# ear-o_devboard.net
KiCad netlist of a schematic drawn in EAGLE
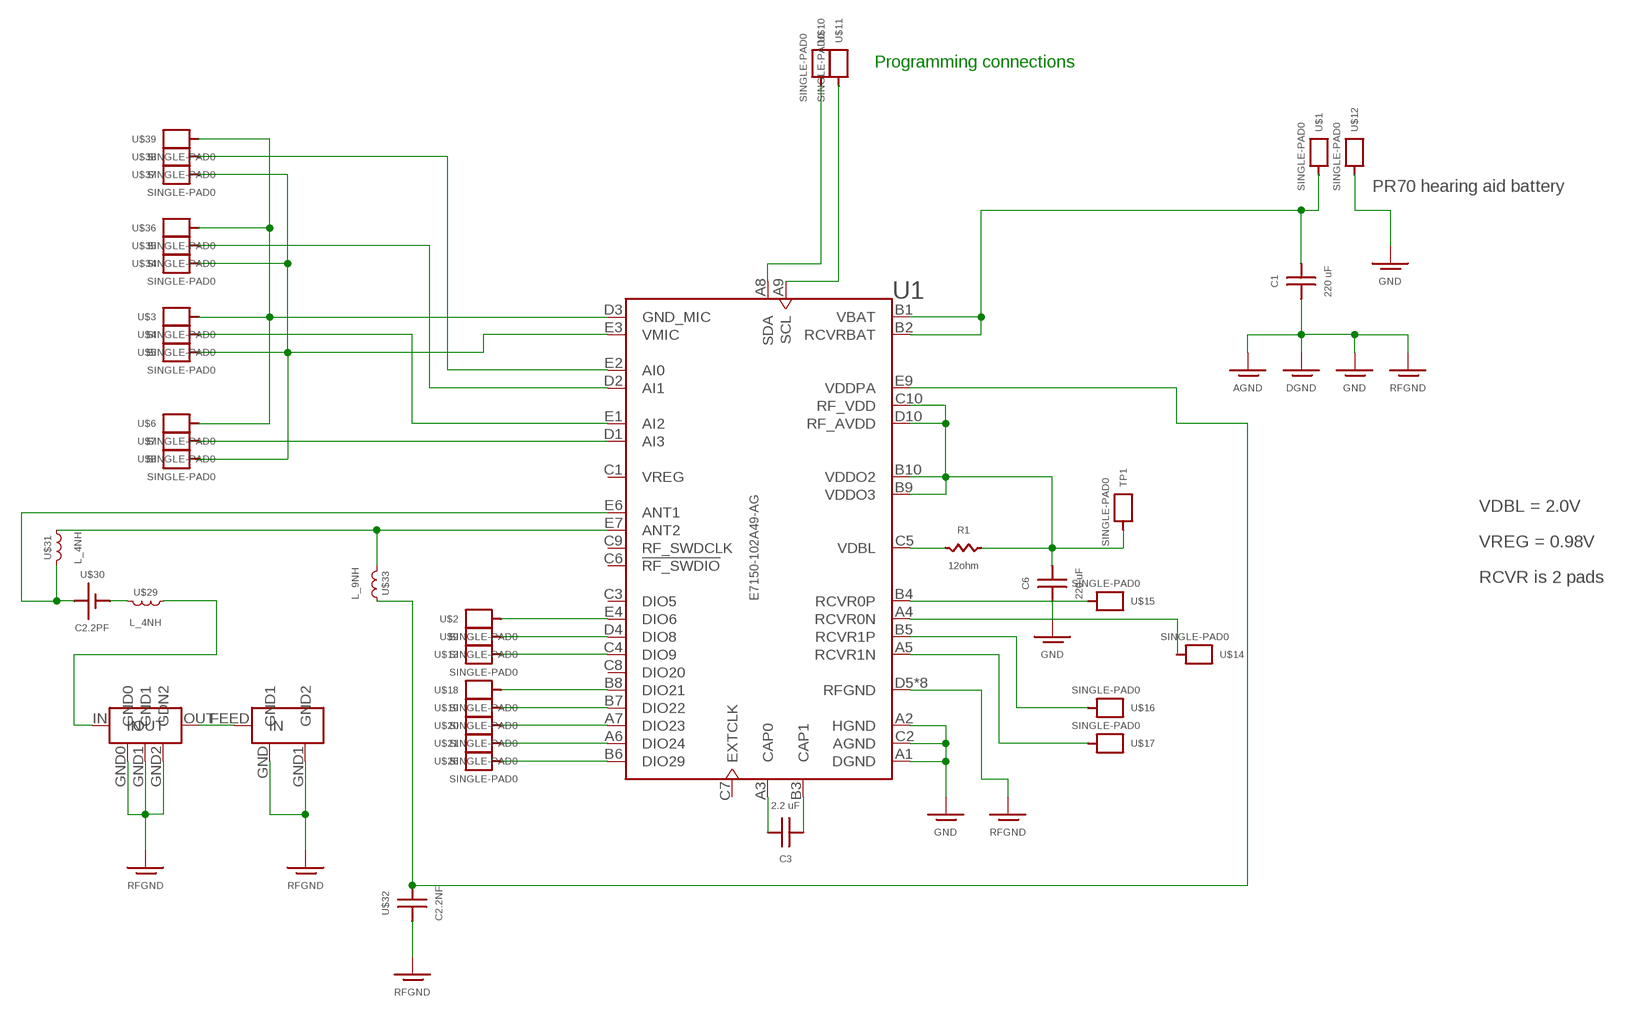
[diagram p0: schematic, sheet 1]

(export (version "E")
  (design (tool "Eeschema 10.0.6"))
  (components
    (comp (ref "C1")
      (value "220 uF")
      (footprint "eagle-import:1206")
      (libsource (lib "eagle-import") (part "C220UF"))
    )
    (comp (ref "C3")
      (value "2.2 uF")
      (footprint "eagle-import:0201")
      (libsource (lib "eagle-import") (part "C2.2UF"))
    )
    (comp (ref "C6")
      (value "220 uF")
      (footprint "eagle-import:1206")
      (libsource (lib "eagle-import") (part "C220UF"))
    )
    (comp (ref "R1")
      (value "12ohm")
      (footprint "eagle-import:0201")
      (libsource (lib "eagle-import") (part "R12OHM"))
    )
    (comp (ref "TP1")
      (value "SINGLE-PAD0")
      (footprint "eagle-import:TH")
      (libsource (lib "eagle-import") (part "SINGLE-PAD0"))
    )
    (comp (ref "U$1")
      (value "SINGLE-PAD0")
      (footprint "eagle-import:TH")
      (libsource (lib "eagle-import") (part "SINGLE-PAD0"))
    )
    (comp (ref "U$2")
      (value "SINGLE-PAD0")
      (footprint "eagle-import:TH")
      (libsource (lib "eagle-import") (part "SINGLE-PAD0"))
    )
    (comp (ref "U$3")
      (value "SINGLE-PAD0")
      (footprint "eagle-import:TH")
      (libsource (lib "eagle-import") (part "SINGLE-PAD0"))
    )
    (comp (ref "U$4")
      (value "SINGLE-PAD0")
      (footprint "eagle-import:TH")
      (libsource (lib "eagle-import") (part "SINGLE-PAD0"))
    )
    (comp (ref "U$5")
      (value "SINGLE-PAD0")
      (footprint "eagle-import:TH")
      (libsource (lib "eagle-import") (part "SINGLE-PAD0"))
    )
    (comp (ref "U$6")
      (value "SINGLE-PAD0")
      (footprint "eagle-import:TH")
      (libsource (lib "eagle-import") (part "SINGLE-PAD0"))
    )
    (comp (ref "U$7")
      (value "SINGLE-PAD0")
      (footprint "eagle-import:TH")
      (libsource (lib "eagle-import") (part "SINGLE-PAD0"))
    )
    (comp (ref "U$8")
      (value "SINGLE-PAD0")
      (footprint "eagle-import:TH")
      (libsource (lib "eagle-import") (part "SINGLE-PAD0"))
    )
    (comp (ref "U$9")
      (value "SINGLE-PAD0")
      (footprint "eagle-import:TH")
      (libsource (lib "eagle-import") (part "SINGLE-PAD0"))
    )
    (comp (ref "U$10")
      (value "SINGLE-PAD0")
      (footprint "eagle-import:TH")
      (libsource (lib "eagle-import") (part "SINGLE-PAD0"))
    )
    (comp (ref "U$11")
      (value "SINGLE-PAD0")
      (footprint "eagle-import:TH")
      (libsource (lib "eagle-import") (part "SINGLE-PAD0"))
    )
    (comp (ref "U$12")
      (value "SINGLE-PAD0")
      (footprint "eagle-import:TH")
      (libsource (lib "eagle-import") (part "SINGLE-PAD0"))
    )
    (comp (ref "U$13")
      (value "SINGLE-PAD0")
      (footprint "eagle-import:TH")
      (libsource (lib "eagle-import") (part "SINGLE-PAD0"))
    )
    (comp (ref "U$14")
      (value "SINGLE-PAD0")
      (footprint "eagle-import:TH")
      (libsource (lib "eagle-import") (part "SINGLE-PAD0"))
    )
    (comp (ref "U$15")
      (value "SINGLE-PAD0")
      (footprint "eagle-import:TH")
      (libsource (lib "eagle-import") (part "SINGLE-PAD0"))
    )
    (comp (ref "U$16")
      (value "SINGLE-PAD0")
      (footprint "eagle-import:TH")
      (libsource (lib "eagle-import") (part "SINGLE-PAD0"))
    )
    (comp (ref "U$17")
      (value "SINGLE-PAD0")
      (footprint "eagle-import:TH")
      (libsource (lib "eagle-import") (part "SINGLE-PAD0"))
    )
    (comp (ref "U$18")
      (value "SINGLE-PAD0")
      (footprint "eagle-import:TH")
      (libsource (lib "eagle-import") (part "SINGLE-PAD0"))
    )
    (comp (ref "U$19")
      (value "SINGLE-PAD0")
      (footprint "eagle-import:TH")
      (libsource (lib "eagle-import") (part "SINGLE-PAD0"))
    )
    (comp (ref "U$20")
      (value "SINGLE-PAD0")
      (footprint "eagle-import:TH")
      (libsource (lib "eagle-import") (part "SINGLE-PAD0"))
    )
    (comp (ref "U$21")
      (value "SINGLE-PAD0")
      (footprint "eagle-import:TH")
      (libsource (lib "eagle-import") (part "SINGLE-PAD0"))
    )
    (comp (ref "U$26")
      (value "SINGLE-PAD0")
      (footprint "eagle-import:TH")
      (libsource (lib "eagle-import") (part "SINGLE-PAD0"))
    )
    (comp (ref "U$27")
      (value "CHIP_ANT")
      (footprint "eagle-import:W3008")
      (libsource (lib "eagle-import") (part "CHIP_ANT"))
    )
    (comp (ref "U$28")
      (value "RF_FILT")
      (footprint "eagle-import:BPFILT")
      (libsource (lib "eagle-import") (part "RF_FILT"))
    )
    (comp (ref "U$29")
      (value "L_4NH")
      (footprint "eagle-import:0402")
      (libsource (lib "eagle-import") (part "L_4NH"))
    )
    (comp (ref "U$30")
      (value "C2.2PF")
      (footprint "eagle-import:0201")
      (libsource (lib "eagle-import") (part "C2.2PF"))
    )
    (comp (ref "U$31")
      (value "L_4NH")
      (footprint "eagle-import:0402")
      (libsource (lib "eagle-import") (part "L_4NH"))
    )
    (comp (ref "U$32")
      (value "C2.2NF")
      (footprint "eagle-import:0201")
      (libsource (lib "eagle-import") (part "C2.2NF"))
    )
    (comp (ref "U$33")
      (value "L_9NH")
      (footprint "eagle-import:0402")
      (libsource (lib "eagle-import") (part "L_9NH"))
    )
    (comp (ref "U$34")
      (value "SINGLE-PAD0")
      (footprint "eagle-import:TH")
      (libsource (lib "eagle-import") (part "SINGLE-PAD0"))
    )
    (comp (ref "U$35")
      (value "SINGLE-PAD0")
      (footprint "eagle-import:TH")
      (libsource (lib "eagle-import") (part "SINGLE-PAD0"))
    )
    (comp (ref "U$36")
      (value "SINGLE-PAD0")
      (footprint "eagle-import:TH")
      (libsource (lib "eagle-import") (part "SINGLE-PAD0"))
    )
    (comp (ref "U$37")
      (value "SINGLE-PAD0")
      (footprint "eagle-import:TH")
      (libsource (lib "eagle-import") (part "SINGLE-PAD0"))
    )
    (comp (ref "U$38")
      (value "SINGLE-PAD0")
      (footprint "eagle-import:TH")
      (libsource (lib "eagle-import") (part "SINGLE-PAD0"))
    )
    (comp (ref "U$39")
      (value "SINGLE-PAD0")
      (footprint "eagle-import:TH")
      (libsource (lib "eagle-import") (part "SINGLE-PAD0"))
    )
    (comp (ref "U1")
      (value "E7150-102A49-AG")
      (footprint "eagle-import:BGA49C69P10X5_739X394X178")
      (fields (field (name "MANUFACTURER") "ON Semiconductor"))
      (libsource (lib "eagle-import") (part "E7150-102A49-AG"))
    )
  )
  (nets
    (net (code "1") (name "/VREG") (class "Default")
      (node (ref "U1") (pin "C1") (pinfunction "VREG_C1") (pintype "power_in"))
    )
    (net (code "2") (name "AGND") (class "Default")
      (node (ref "C1") (pin "P$1") (pinfunction "1_P$1") (pintype "passive"))
      (node (ref "C6") (pin "P$1") (pinfunction "1_P$1") (pintype "passive"))
      (node (ref "U$12") (pin "P$1") (pinfunction "1_P$1") (pintype "bidirectional"))
      (node (ref "U$27") (pin "GND") (pinfunction "GND1_GND") (pintype "bidirectional"))
      (node (ref "U$27") (pin "GND1") (pinfunction "GND2_GND1") (pintype "bidirectional"))
      (node (ref "U$28") (pin "GND0") (pinfunction "GND0_GND0") (pintype "bidirectional"))
      (node (ref "U$28") (pin "GND1") (pinfunction "GND1_GND1") (pintype "bidirectional"))
      (node (ref "U$28") (pin "GND2") (pinfunction "GDN2_GND2") (pintype "bidirectional"))
      (node (ref "U$29") (pin "2") (pinfunction "2_2") (pintype "passive"))
      (node (ref "U$30") (pin "P$1") (pinfunction "GND_P$1") (pintype "power_in"))
      (node (ref "U$32") (pin "P$1") (pinfunction "1_P$1") (pintype "passive"))
      (node (ref "U1") (pin "A1") (pinfunction "DGND_A1") (pintype "power_in"))
      (node (ref "U1") (pin "A2") (pinfunction "HGND_A2") (pintype "power_in"))
      (node (ref "U1") (pin "C2") (pinfunction "AGND_C2") (pintype "power_in"))
      (node (ref "U1") (pin "D5") (pinfunction "RFGND_D5") (pintype "power_in"))
      (node (ref "U1") (pin "D6") (pinfunction "RFGND_D6") (pintype "power_in"))
      (node (ref "U1") (pin "D7") (pinfunction "RFGND_D7") (pintype "power_in"))
      (node (ref "U1") (pin "D8") (pinfunction "RFGND_D8") (pintype "power_in"))
      (node (ref "U1") (pin "D9") (pinfunction "RFGND_D9") (pintype "power_in"))
      (node (ref "U1") (pin "E10") (pinfunction "RFGND_E10") (pintype "power_in"))
      (node (ref "U1") (pin "E5") (pinfunction "RFGND_E5") (pintype "power_in"))
      (node (ref "U1") (pin "E8") (pinfunction "RFGND_E8") (pintype "power_in"))
    )
    (net (code "3") (name "Net-(C1-2)") (class "Default")
      (node (ref "C1") (pin "P$2") (pinfunction "2_P$2") (pintype "passive"))
      (node (ref "U$1") (pin "P$1") (pinfunction "1_P$1") (pintype "bidirectional"))
      (node (ref "U1") (pin "B1") (pinfunction "VBAT_B1") (pintype "power_in"))
      (node (ref "U1") (pin "B2") (pinfunction "RCVRBAT_B2") (pintype "power_in"))
    )
    (net (code "4") (name "Net-(C3-1)") (class "Default")
      (node (ref "C3") (pin "P$1") (pinfunction "1_P$1") (pintype "passive"))
      (node (ref "U1") (pin "B3") (pinfunction "CAP1_B3") (pintype "bidirectional"))
    )
    (net (code "5") (name "Net-(C3-2)") (class "Default")
      (node (ref "C3") (pin "P$2") (pinfunction "2_P$2") (pintype "passive"))
      (node (ref "U1") (pin "A3") (pinfunction "CAP0_A3") (pintype "bidirectional"))
    )
    (net (code "6") (name "Net-(C6-2)") (class "Default")
      (node (ref "C6") (pin "P$2") (pinfunction "2_P$2") (pintype "passive"))
      (node (ref "R1") (pin "P$2") (pinfunction "P$2_P$2") (pintype "bidirectional"))
      (node (ref "TP1") (pin "P$1") (pinfunction "1_P$1") (pintype "bidirectional"))
      (node (ref "U1") (pin "B10") (pinfunction "VDDO2_B10") (pintype "power_in"))
      (node (ref "U1") (pin "B9") (pinfunction "VDDO3_B9") (pintype "power_in"))
      (node (ref "U1") (pin "C10") (pinfunction "RF_VDD_C10") (pintype "power_in"))
      (node (ref "U1") (pin "D10") (pinfunction "RF_AVDD_D10") (pintype "power_in"))
    )
    (net (code "7") (name "Net-(U$2-1)") (class "Default")
      (node (ref "U$2") (pin "P$1") (pinfunction "1_P$1") (pintype "bidirectional"))
      (node (ref "U1") (pin "E4") (pinfunction "DIO6_E4") (pintype "bidirectional"))
    )
    (net (code "8") (name "Net-(U$3-1)") (class "Default")
      (node (ref "U$3") (pin "P$1") (pinfunction "1_P$1") (pintype "bidirectional"))
      (node (ref "U$36") (pin "P$1") (pinfunction "1_P$1") (pintype "bidirectional"))
      (node (ref "U$39") (pin "P$1") (pinfunction "1_P$1") (pintype "bidirectional"))
      (node (ref "U$6") (pin "P$1") (pinfunction "1_P$1") (pintype "bidirectional"))
      (node (ref "U1") (pin "D3") (pinfunction "GND_MIC_D3") (pintype "power_in"))
    )
    (net (code "9") (name "Net-(U$4-1)") (class "Default")
      (node (ref "U$4") (pin "P$1") (pinfunction "1_P$1") (pintype "bidirectional"))
      (node (ref "U1") (pin "E1") (pinfunction "AI2_E1") (pintype "input"))
    )
    (net (code "10") (name "Net-(U$7-1)") (class "Default")
      (node (ref "U$7") (pin "P$1") (pinfunction "1_P$1") (pintype "bidirectional"))
      (node (ref "U1") (pin "D1") (pinfunction "AI3_D1") (pintype "input"))
    )
    (net (code "11") (name "Net-(U$9-1)") (class "Default")
      (node (ref "U$9") (pin "P$1") (pinfunction "1_P$1") (pintype "bidirectional"))
      (node (ref "U1") (pin "D4") (pinfunction "DIO8_D4") (pintype "bidirectional"))
    )
    (net (code "12") (name "Net-(U$10-1)") (class "Default")
      (node (ref "U$10") (pin "P$1") (pinfunction "1_P$1") (pintype "bidirectional"))
      (node (ref "U1") (pin "A8") (pinfunction "SDA_A8") (pintype "bidirectional"))
    )
    (net (code "13") (name "Net-(U$11-1)") (class "Default")
      (node (ref "U$11") (pin "P$1") (pinfunction "1_P$1") (pintype "bidirectional"))
      (node (ref "U1") (pin "A9") (pinfunction "SCL_A9") (pintype "input"))
    )
    (net (code "14") (name "Net-(U$13-1)") (class "Default")
      (node (ref "U$13") (pin "P$1") (pinfunction "1_P$1") (pintype "bidirectional"))
      (node (ref "U1") (pin "C4") (pinfunction "DIO9_C4") (pintype "bidirectional"))
    )
    (net (code "15") (name "Net-(U$14-1)") (class "Default")
      (node (ref "U$14") (pin "P$1") (pinfunction "1_P$1") (pintype "bidirectional"))
      (node (ref "U1") (pin "A4") (pinfunction "RCVR0N_A4") (pintype "output"))
    )
    (net (code "16") (name "Net-(U$15-1)") (class "Default")
      (node (ref "U$15") (pin "P$1") (pinfunction "1_P$1") (pintype "bidirectional"))
      (node (ref "U1") (pin "B4") (pinfunction "RCVR0P_B4") (pintype "output"))
    )
    (net (code "17") (name "Net-(U$16-1)") (class "Default")
      (node (ref "U$16") (pin "P$1") (pinfunction "1_P$1") (pintype "bidirectional"))
      (node (ref "U1") (pin "B5") (pinfunction "RCVR1P_B5") (pintype "output"))
    )
    (net (code "18") (name "Net-(U$17-1)") (class "Default")
      (node (ref "U$17") (pin "P$1") (pinfunction "1_P$1") (pintype "bidirectional"))
      (node (ref "U1") (pin "A5") (pinfunction "RCVR1N_A5") (pintype "output"))
    )
    (net (code "19") (name "Net-(U$18-1)") (class "Default")
      (node (ref "U$18") (pin "P$1") (pinfunction "1_P$1") (pintype "bidirectional"))
      (node (ref "U1") (pin "B8") (pinfunction "DIO21_B8") (pintype "bidirectional"))
    )
    (net (code "20") (name "Net-(U$19-1)") (class "Default")
      (node (ref "U$19") (pin "P$1") (pinfunction "1_P$1") (pintype "bidirectional"))
      (node (ref "U1") (pin "B7") (pinfunction "DIO22_B7") (pintype "bidirectional"))
    )
    (net (code "21") (name "Net-(U$20-1)") (class "Default")
      (node (ref "U$20") (pin "P$1") (pinfunction "1_P$1") (pintype "bidirectional"))
      (node (ref "U1") (pin "A7") (pinfunction "DIO23_A7") (pintype "bidirectional"))
    )
    (net (code "22") (name "Net-(U$21-1)") (class "Default")
      (node (ref "U$21") (pin "P$1") (pinfunction "1_P$1") (pintype "bidirectional"))
      (node (ref "U1") (pin "A6") (pinfunction "DIO24_A6") (pintype "bidirectional"))
    )
    (net (code "23") (name "Net-(U$26-1)") (class "Default")
      (node (ref "U$26") (pin "P$1") (pinfunction "1_P$1") (pintype "bidirectional"))
      (node (ref "U1") (pin "B6") (pinfunction "DIO29_B6") (pintype "bidirectional"))
    )
    (net (code "24") (name "Net-(U$27-IN)") (class "Default")
      (node (ref "U$27") (pin "FEED") (pinfunction "IN_FEED") (pintype "bidirectional"))
      (node (ref "U$28") (pin "OUT") (pinfunction "OUT_OUT") (pintype "bidirectional"))
    )
    (net (code "25") (name "Net-(U$28-PadIN)") (class "Default")
      (node (ref "U$28") (pin "IN") (pinfunction "IN_IN") (pintype "bidirectional"))
      (node (ref "U$29") (pin "1") (pinfunction "1_1") (pintype "passive"))
    )
    (net (code "26") (name "Net-(U$30-P1.4V)") (class "Default")
      (node (ref "U$30") (pin "P$2") (pinfunction "P1.4V_P$2") (pintype "power_in"))
      (node (ref "U$31") (pin "2") (pinfunction "2_2") (pintype "passive"))
      (node (ref "U1") (pin "E6") (pinfunction "ANT1_E6") (pintype "bidirectional"))
    )
    (net (code "27") (name "Net-(U$32-2)") (class "Default")
      (node (ref "U$32") (pin "P$2") (pinfunction "2_P$2") (pintype "passive"))
      (node (ref "U$33") (pin "1") (pinfunction "1_1") (pintype "passive"))
      (node (ref "U1") (pin "E9") (pinfunction "VDDPA_E9") (pintype "power_in"))
    )
    (net (code "28") (name "Net-(U$34-1)") (class "Default")
      (node (ref "U$34") (pin "P$1") (pinfunction "1_P$1") (pintype "bidirectional"))
      (node (ref "U$37") (pin "P$1") (pinfunction "1_P$1") (pintype "bidirectional"))
      (node (ref "U$5") (pin "P$1") (pinfunction "1_P$1") (pintype "bidirectional"))
      (node (ref "U$8") (pin "P$1") (pinfunction "1_P$1") (pintype "bidirectional"))
      (node (ref "U1") (pin "E3") (pinfunction "VMIC_E3") (pintype "power_in"))
    )
    (net (code "29") (name "Net-(U$35-1)") (class "Default")
      (node (ref "U$35") (pin "P$1") (pinfunction "1_P$1") (pintype "bidirectional"))
      (node (ref "U1") (pin "D2") (pinfunction "AI1_D2") (pintype "input"))
    )
    (net (code "30") (name "Net-(U$38-1)") (class "Default")
      (node (ref "U$38") (pin "P$1") (pinfunction "1_P$1") (pintype "bidirectional"))
      (node (ref "U1") (pin "E2") (pinfunction "AI0_E2") (pintype "input"))
    )
    (net (code "31") (name "Net-(U1-ANT2)") (class "Default")
      (node (ref "U$31") (pin "1") (pinfunction "1_1") (pintype "passive"))
      (node (ref "U$33") (pin "2") (pinfunction "2_2") (pintype "passive"))
      (node (ref "U1") (pin "E7") (pinfunction "ANT2_E7") (pintype "bidirectional"))
    )
    (net (code "32") (name "Net-(U1-VDBL)") (class "Default")
      (node (ref "R1") (pin "P$1") (pinfunction "P$1_P$1") (pintype "bidirectional"))
      (node (ref "U1") (pin "C5") (pinfunction "VDBL_C5") (pintype "output"))
    )
    (net (code "33") (name "unconnected-(U1-DIO5-PadC3)") (class "Default")
      (node (ref "U1") (pin "C3") (pinfunction "DIO5_C3") (pintype "bidirectional"))
    )
    (net (code "34") (name "unconnected-(U1-DIO20-PadC8)") (class "Default")
      (node (ref "U1") (pin "C8") (pinfunction "DIO20_C8") (pintype "bidirectional"))
    )
    (net (code "35") (name "unconnected-(U1-EXTCLK-PadC7)") (class "Default")
      (node (ref "U1") (pin "C7") (pinfunction "EXTCLK_C7") (pintype "input"))
    )
    (net (code "36") (name "unconnected-(U1-RF_SWDCLK-PadC9)") (class "Default")
      (node (ref "U1") (pin "C9") (pinfunction "RF_SWDCLK_C9") (pintype "bidirectional"))
    )
    (net (code "37") (name "unconnected-(U1-~{RF_SWDIO}-PadC6)") (class "Default")
      (node (ref "U1") (pin "C6") (pinfunction "~{RF_SWDIO}_C6") (pintype "bidirectional"))
    )
  )
)
